# F1-T12_compact.net
KiCad netlist of a schematic drawn in EAGLE
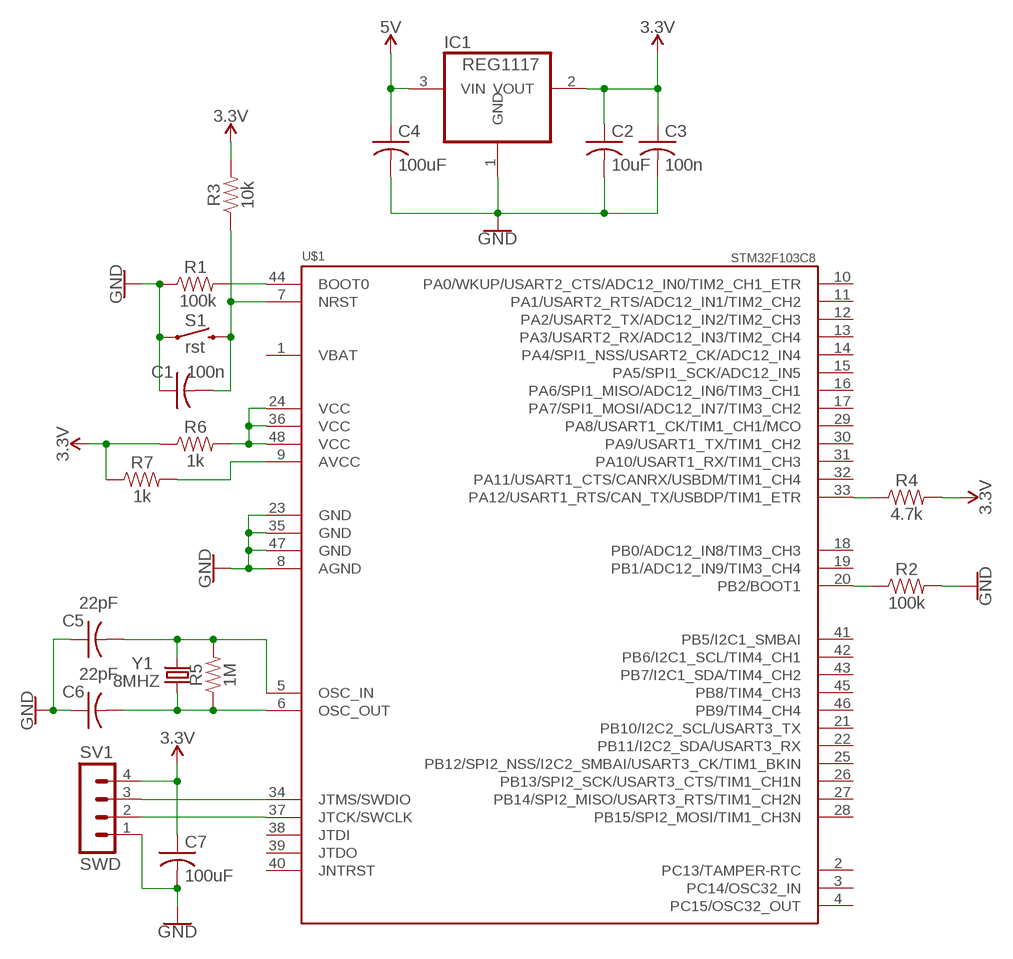
[diagram p0: schematic, sheet 1]

(export (version "E")
  (design (tool "Eeschema 10.0.6"))
  (components
    (comp (ref "C1")
      (value "100n")
      (footprint "eagle-import:1206")
      (libsource (lib "eagle-import") (part "C_USD"))
    )
    (comp (ref "C2")
      (value "10uF")
      (footprint "eagle-import:1206")
      (libsource (lib "eagle-import") (part "C_USD"))
    )
    (comp (ref "C3")
      (value "100n")
      (footprint "eagle-import:1206")
      (libsource (lib "eagle-import") (part "C_USD"))
    )
    (comp (ref "C4")
      (value "100uF")
      (footprint "eagle-import:1812")
      (libsource (lib "eagle-import") (part "C_USF"))
    )
    (comp (ref "C5")
      (value "22pF")
      (footprint "eagle-import:1206")
      (libsource (lib "eagle-import") (part "C_USD"))
    )
    (comp (ref "C6")
      (value "22pF")
      (footprint "eagle-import:1206")
      (libsource (lib "eagle-import") (part "C_USD"))
    )
    (comp (ref "C7")
      (value "100uF")
      (footprint "eagle-import:1812")
      (libsource (lib "eagle-import") (part "C_USF"))
    )
    (comp (ref "IC1")
      (value "REG1117")
      (footprint "eagle-import:SOT223")
      (libsource (lib "eagle-import") (part "REG1117"))
    )
    (comp (ref "R1")
      (value "100k")
      (footprint "eagle-import:1206")
      (libsource (lib "eagle-import") (part "RESISTOR1206"))
    )
    (comp (ref "R2")
      (value "100k")
      (footprint "eagle-import:1206")
      (libsource (lib "eagle-import") (part "RESISTOR1206"))
    )
    (comp (ref "R3")
      (value "10k")
      (footprint "eagle-import:1206")
      (libsource (lib "eagle-import") (part "RESISTOR1206"))
    )
    (comp (ref "R4")
      (value "4.7k")
      (footprint "eagle-import:1206")
      (libsource (lib "eagle-import") (part "RESISTOR1206"))
    )
    (comp (ref "R5")
      (value "1M")
      (footprint "eagle-import:1206")
      (libsource (lib "eagle-import") (part "RESISTOR1206"))
    )
    (comp (ref "R6")
      (value "1k")
      (footprint "eagle-import:1206")
      (libsource (lib "eagle-import") (part "RESISTOR1206"))
    )
    (comp (ref "R7")
      (value "1k")
      (footprint "eagle-import:1206")
      (libsource (lib "eagle-import") (part "RESISTOR1206"))
    )
    (comp (ref "S1")
      (value "rst")
      (footprint "eagle-import:TACTILE_SWITCH_SMD_4.6X2.8MM")
      (libsource (lib "eagle-import") (part "MOMENTARY-SWITCH-SPST-SMD-4.6X2.8MM"))
    )
    (comp (ref "SV1")
      (value "SWD")
      (footprint "eagle-import:MA04-1")
      (libsource (lib "eagle-import") (part "MA04-1"))
    )
    (comp (ref "U$1")
      (value "STM32F103C8")
      (footprint "eagle-import:LQFP48-7X7")
      (libsource (lib "eagle-import") (part "STM32F103C8"))
    )
    (comp (ref "Y1")
      (value "8MHZ")
      (footprint "eagle-import:HC49US")
      (libsource (lib "eagle-import") (part "CRYSTALHC49US"))
    )
  )
  (nets
    (net (code "1") (name "/VBAT") (class "Default")
      (node (ref "U$1") (pin "1") (pinfunction "VBAT_1") (pintype "power_in"))
    )
    (net (code "2") (name "3.3V") (class "Default")
      (node (ref "C2") (pin "1") (pinfunction "1_1") (pintype "passive"))
      (node (ref "C3") (pin "1") (pinfunction "1_1") (pintype "passive"))
      (node (ref "C7") (pin "1") (pinfunction "1_1") (pintype "passive"))
      (node (ref "IC1") (pin "2") (pinfunction "VOUT_2") (pintype "output"))
      (node (ref "R3") (pin "2") (pinfunction "2_2") (pintype "passive"))
      (node (ref "R4") (pin "2") (pinfunction "2_2") (pintype "passive"))
      (node (ref "R6") (pin "1") (pinfunction "1_1") (pintype "passive"))
      (node (ref "R7") (pin "1") (pinfunction "1_1") (pintype "passive"))
      (node (ref "SV1") (pin "4") (pinfunction "4_4") (pintype "passive"))
    )
    (net (code "3") (name "5V") (class "Default")
      (node (ref "C4") (pin "1") (pinfunction "1_1") (pintype "passive"))
      (node (ref "IC1") (pin "3") (pinfunction "VIN_3") (pintype "input"))
    )
    (net (code "4") (name "GND") (class "Default")
      (node (ref "C1") (pin "1") (pinfunction "1_1") (pintype "passive"))
      (node (ref "C2") (pin "2") (pinfunction "2_2") (pintype "passive"))
      (node (ref "C3") (pin "2") (pinfunction "2_2") (pintype "passive"))
      (node (ref "C4") (pin "2") (pinfunction "2_2") (pintype "passive"))
      (node (ref "C5") (pin "1") (pinfunction "1_1") (pintype "passive"))
      (node (ref "C6") (pin "1") (pinfunction "1_1") (pintype "passive"))
      (node (ref "C7") (pin "2") (pinfunction "2_2") (pintype "passive"))
      (node (ref "IC1") (pin "1") (pinfunction "GND_1") (pintype "power_in"))
      (node (ref "R1") (pin "1") (pinfunction "1_1") (pintype "passive"))
      (node (ref "R2") (pin "2") (pinfunction "2_2") (pintype "passive"))
      (node (ref "S1") (pin "1") (pinfunction "1_1") (pintype "passive"))
      (node (ref "S1") (pin "2") (pinfunction "1_2") (pintype "passive"))
      (node (ref "SV1") (pin "1") (pinfunction "1_1") (pintype "passive"))
      (node (ref "U$1") (pin "23") (pinfunction "GND_23") (pintype "power_in"))
      (node (ref "U$1") (pin "35") (pinfunction "GND_35") (pintype "power_in"))
      (node (ref "U$1") (pin "47") (pinfunction "GND_47") (pintype "power_in"))
      (node (ref "U$1") (pin "8") (pinfunction "AGND_8") (pintype "power_in"))
    )
    (net (code "5") (name "Net-(R6-Pad2)") (class "Default")
      (node (ref "R6") (pin "2") (pinfunction "2_2") (pintype "passive"))
      (node (ref "U$1") (pin "24") (pinfunction "VCC_24") (pintype "power_in"))
      (node (ref "U$1") (pin "36") (pinfunction "VCC_36") (pintype "power_in"))
      (node (ref "U$1") (pin "48") (pinfunction "VCC_48") (pintype "power_in"))
    )
    (net (code "6") (name "Net-(U$1-AVCC)") (class "Default")
      (node (ref "R7") (pin "2") (pinfunction "2_2") (pintype "passive"))
      (node (ref "U$1") (pin "9") (pinfunction "AVCC_9") (pintype "power_in"))
    )
    (net (code "7") (name "Net-(U$1-BOOT0)") (class "Default")
      (node (ref "R1") (pin "2") (pinfunction "2_2") (pintype "passive"))
      (node (ref "U$1") (pin "44") (pinfunction "BOOT0_44") (pintype "bidirectional"))
    )
    (net (code "8") (name "Net-(U$1-JTCK{slash}SWCLK)") (class "Default")
      (node (ref "SV1") (pin "2") (pinfunction "2_2") (pintype "passive"))
      (node (ref "U$1") (pin "37") (pinfunction "JTCK/SWCLK_37") (pintype "bidirectional"))
    )
    (net (code "9") (name "Net-(U$1-JTMS{slash}SWDIO)") (class "Default")
      (node (ref "SV1") (pin "3") (pinfunction "3_3") (pintype "passive"))
      (node (ref "U$1") (pin "34") (pinfunction "JTMS/SWDIO_34") (pintype "bidirectional"))
    )
    (net (code "10") (name "Net-(U$1-NRST)") (class "Default")
      (node (ref "C1") (pin "2") (pinfunction "2_2") (pintype "passive"))
      (node (ref "R3") (pin "1") (pinfunction "1_1") (pintype "passive"))
      (node (ref "S1") (pin "3") (pinfunction "2_3") (pintype "passive"))
      (node (ref "S1") (pin "4") (pinfunction "2_4") (pintype "passive"))
      (node (ref "U$1") (pin "7") (pinfunction "NRST_7") (pintype "bidirectional"))
    )
    (net (code "11") (name "Net-(U$1-OSC_IN)") (class "Default")
      (node (ref "C5") (pin "2") (pinfunction "2_2") (pintype "passive"))
      (node (ref "R5") (pin "2") (pinfunction "2_2") (pintype "passive"))
      (node (ref "U$1") (pin "5") (pinfunction "OSC_IN_5") (pintype "input"))
      (node (ref "Y1") (pin "2") (pinfunction "2_2") (pintype "passive"))
    )
    (net (code "12") (name "Net-(U$1-OSC_OUT)") (class "Default")
      (node (ref "C6") (pin "2") (pinfunction "2_2") (pintype "passive"))
      (node (ref "R5") (pin "1") (pinfunction "1_1") (pintype "passive"))
      (node (ref "U$1") (pin "6") (pinfunction "OSC_OUT_6") (pintype "output"))
      (node (ref "Y1") (pin "1") (pinfunction "1_1") (pintype "passive"))
    )
    (net (code "13") (name "Net-(U$1-PA12{slash}USART1_RTS{slash}CAN_TX{slash}USBDP{slash}TIM1_ETR)") (class "Default")
      (node (ref "R4") (pin "1") (pinfunction "1_1") (pintype "passive"))
      (node (ref "U$1") (pin "33") (pinfunction "PA12/USART1_RTS/CAN_TX/USBDP/TIM1_ETR_33") (pintype "bidirectional"))
    )
    (net (code "14") (name "Net-(U$1-PB2{slash}BOOT1)") (class "Default")
      (node (ref "R2") (pin "1") (pinfunction "1_1") (pintype "passive"))
      (node (ref "U$1") (pin "20") (pinfunction "PB2/BOOT1_20") (pintype "bidirectional"))
    )
    (net (code "15") (name "unconnected-(U$1-JNTRST-Pad40)") (class "Default")
      (node (ref "U$1") (pin "40") (pinfunction "JNTRST_40") (pintype "bidirectional"))
    )
    (net (code "16") (name "unconnected-(U$1-JTDI-Pad38)") (class "Default")
      (node (ref "U$1") (pin "38") (pinfunction "JTDI_38") (pintype "bidirectional"))
    )
    (net (code "17") (name "unconnected-(U$1-JTDO-Pad39)") (class "Default")
      (node (ref "U$1") (pin "39") (pinfunction "JTDO_39") (pintype "bidirectional"))
    )
    (net (code "18") (name "unconnected-(U$1-PA0{slash}WKUP{slash}USART2_CTS{slash}ADC12_IN0{slash}TIM2_CH1_ETR-Pad10)") (class "Default")
      (node (ref "U$1") (pin "10") (pinfunction "PA0/WKUP/USART2_CTS/ADC12_IN0/TIM2_CH1_ETR_10") (pintype "bidirectional"))
    )
    (net (code "19") (name "unconnected-(U$1-PA1{slash}USART2_RTS{slash}ADC12_IN1{slash}TIM2_CH2-Pad11)") (class "Default")
      (node (ref "U$1") (pin "11") (pinfunction "PA1/USART2_RTS/ADC12_IN1/TIM2_CH2_11") (pintype "bidirectional"))
    )
    (net (code "20") (name "unconnected-(U$1-PA2{slash}USART2_TX{slash}ADC12_IN2{slash}TIM2_CH3-Pad12)") (class "Default")
      (node (ref "U$1") (pin "12") (pinfunction "PA2/USART2_TX/ADC12_IN2/TIM2_CH3_12") (pintype "bidirectional"))
    )
    (net (code "21") (name "unconnected-(U$1-PA3{slash}USART2_RX{slash}ADC12_IN3{slash}TIM2_CH4-Pad13)") (class "Default")
      (node (ref "U$1") (pin "13") (pinfunction "PA3/USART2_RX/ADC12_IN3/TIM2_CH4_13") (pintype "bidirectional"))
    )
    (net (code "22") (name "unconnected-(U$1-PA4{slash}SPI1_NSS{slash}USART2_CK{slash}ADC12_IN4-Pad14)") (class "Default")
      (node (ref "U$1") (pin "14") (pinfunction "PA4/SPI1_NSS/USART2_CK/ADC12_IN4_14") (pintype "bidirectional"))
    )
    (net (code "23") (name "unconnected-(U$1-PA5{slash}SPI1_SCK{slash}ADC12_IN5-Pad15)") (class "Default")
      (node (ref "U$1") (pin "15") (pinfunction "PA5/SPI1_SCK/ADC12_IN5_15") (pintype "bidirectional"))
    )
    (net (code "24") (name "unconnected-(U$1-PA6{slash}SPI1_MISO{slash}ADC12_IN6{slash}TIM3_CH1-Pad16)") (class "Default")
      (node (ref "U$1") (pin "16") (pinfunction "PA6/SPI1_MISO/ADC12_IN6/TIM3_CH1_16") (pintype "bidirectional"))
    )
    (net (code "25") (name "unconnected-(U$1-PA7{slash}SPI1_MOSI{slash}ADC12_IN7{slash}TIM3_CH2-Pad17)") (class "Default")
      (node (ref "U$1") (pin "17") (pinfunction "PA7/SPI1_MOSI/ADC12_IN7/TIM3_CH2_17") (pintype "bidirectional"))
    )
    (net (code "26") (name "unconnected-(U$1-PA8{slash}USART1_CK{slash}TIM1_CH1{slash}MCO-Pad29)") (class "Default")
      (node (ref "U$1") (pin "29") (pinfunction "PA8/USART1_CK/TIM1_CH1/MCO_29") (pintype "bidirectional"))
    )
    (net (code "27") (name "unconnected-(U$1-PA9{slash}USART1_TX{slash}TIM1_CH2-Pad30)") (class "Default")
      (node (ref "U$1") (pin "30") (pinfunction "PA9/USART1_TX/TIM1_CH2_30") (pintype "bidirectional"))
    )
    (net (code "28") (name "unconnected-(U$1-PA10{slash}USART1_RX{slash}TIM1_CH3-Pad31)") (class "Default")
      (node (ref "U$1") (pin "31") (pinfunction "PA10/USART1_RX/TIM1_CH3_31") (pintype "bidirectional"))
    )
    (net (code "29") (name "unconnected-(U$1-PA11{slash}USART1_CTS{slash}CANRX{slash}USBDM{slash}TIM1_CH4-Pad32)") (class "Default")
      (node (ref "U$1") (pin "32") (pinfunction "PA11/USART1_CTS/CANRX/USBDM/TIM1_CH4_32") (pintype "bidirectional"))
    )
    (net (code "30") (name "unconnected-(U$1-PB0{slash}ADC12_IN8{slash}TIM3_CH3-Pad18)") (class "Default")
      (node (ref "U$1") (pin "18") (pinfunction "PB0/ADC12_IN8/TIM3_CH3_18") (pintype "bidirectional"))
    )
    (net (code "31") (name "unconnected-(U$1-PB1{slash}ADC12_IN9{slash}TIM3_CH4-Pad19)") (class "Default")
      (node (ref "U$1") (pin "19") (pinfunction "PB1/ADC12_IN9/TIM3_CH4_19") (pintype "bidirectional"))
    )
    (net (code "32") (name "unconnected-(U$1-PB5{slash}I2C1_SMBAI-Pad41)") (class "Default")
      (node (ref "U$1") (pin "41") (pinfunction "PB5/I2C1_SMBAI_41") (pintype "bidirectional"))
    )
    (net (code "33") (name "unconnected-(U$1-PB6{slash}I2C1_SCL{slash}TIM4_CH1-Pad42)") (class "Default")
      (node (ref "U$1") (pin "42") (pinfunction "PB6/I2C1_SCL/TIM4_CH1_42") (pintype "bidirectional"))
    )
    (net (code "34") (name "unconnected-(U$1-PB7{slash}I2C1_SDA{slash}TIM4_CH2-Pad43)") (class "Default")
      (node (ref "U$1") (pin "43") (pinfunction "PB7/I2C1_SDA/TIM4_CH2_43") (pintype "bidirectional"))
    )
    (net (code "35") (name "unconnected-(U$1-PB8{slash}TIM4_CH3-Pad45)") (class "Default")
      (node (ref "U$1") (pin "45") (pinfunction "PB8/TIM4_CH3_45") (pintype "bidirectional"))
    )
    (net (code "36") (name "unconnected-(U$1-PB9{slash}TIM4_CH4-Pad46)") (class "Default")
      (node (ref "U$1") (pin "46") (pinfunction "PB9/TIM4_CH4_46") (pintype "bidirectional"))
    )
    (net (code "37") (name "unconnected-(U$1-PB10{slash}I2C2_SCL{slash}USART3_TX-Pad21)") (class "Default")
      (node (ref "U$1") (pin "21") (pinfunction "PB10/I2C2_SCL/USART3_TX_21") (pintype "bidirectional"))
    )
    (net (code "38") (name "unconnected-(U$1-PB11{slash}I2C2_SDA{slash}USART3_RX-Pad22)") (class "Default")
      (node (ref "U$1") (pin "22") (pinfunction "PB11/I2C2_SDA/USART3_RX_22") (pintype "bidirectional"))
    )
    (net (code "39") (name "unconnected-(U$1-PB12{slash}SPI2_NSS{slash}I2C2_SMBAI{slash}USART3_CK{slash}TIM1_BKIN-Pad25)") (class "Default")
      (node (ref "U$1") (pin "25") (pinfunction "PB12/SPI2_NSS/I2C2_SMBAI/USART3_CK/TIM1_BKIN_25") (pintype "bidirectional"))
    )
    (net (code "40") (name "unconnected-(U$1-PB13{slash}SPI2_SCK{slash}USART3_CTS{slash}TIM1_CH1N-Pad26)") (class "Default")
      (node (ref "U$1") (pin "26") (pinfunction "PB13/SPI2_SCK/USART3_CTS/TIM1_CH1N_26") (pintype "bidirectional"))
    )
    (net (code "41") (name "unconnected-(U$1-PB14{slash}SPI2_MISO{slash}USART3_RTS{slash}TIM1_CH2N-Pad27)") (class "Default")
      (node (ref "U$1") (pin "27") (pinfunction "PB14/SPI2_MISO/USART3_RTS/TIM1_CH2N_27") (pintype "bidirectional"))
    )
    (net (code "42") (name "unconnected-(U$1-PB15{slash}SPI2_MOSI{slash}TIM1_CH3N-Pad28)") (class "Default")
      (node (ref "U$1") (pin "28") (pinfunction "PB15/SPI2_MOSI/TIM1_CH3N_28") (pintype "bidirectional"))
    )
    (net (code "43") (name "unconnected-(U$1-PC13{slash}TAMPER-RTC-Pad2)") (class "Default")
      (node (ref "U$1") (pin "2") (pinfunction "PC13/TAMPER-RTC_2") (pintype "bidirectional"))
    )
    (net (code "44") (name "unconnected-(U$1-PC14{slash}OSC32_IN-Pad3)") (class "Default")
      (node (ref "U$1") (pin "3") (pinfunction "PC14/OSC32_IN_3") (pintype "bidirectional"))
    )
    (net (code "45") (name "unconnected-(U$1-PC15{slash}OSC32_OUT-Pad4)") (class "Default")
      (node (ref "U$1") (pin "4") (pinfunction "PC15/OSC32_OUT_4") (pintype "bidirectional"))
    )
  )
)
